# Connector.net
KiCad netlist of a schematic drawn in Altium Designer
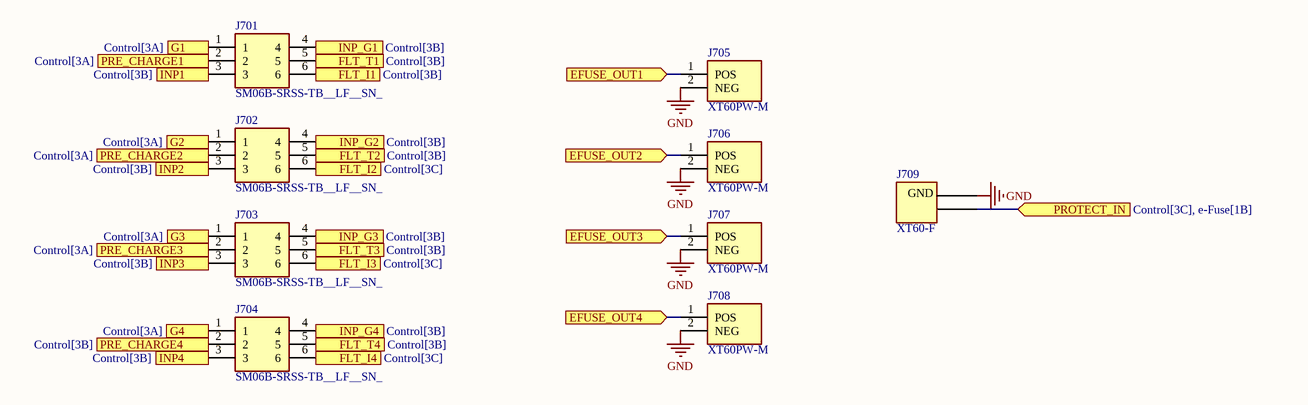
[diagram p0: Connector.SchDoc]

(export (version "E")
  (design (tool "Eeschema 10.0.6"))
  (components
    (comp (ref "J701")
      (value "SM06B-SRSS-TB__LF__SN_")
      (footprint "SamacSys:SM06B-SRSS-TB")
      (description "Connector")
      (fields (field (name "MANUFACTURER_PART_NUMBER") "SM06B-SRSS-TB (LF)(SN)"))
      (libsource (lib "*") (part "SM06B-SRSS-TB__LF__SN_"))
    )
    (comp (ref "J702")
      (value "SM06B-SRSS-TB__LF__SN_")
      (footprint "SamacSys:SM06B-SRSS-TB")
      (description "Connector")
      (fields (field (name "MANUFACTURER_PART_NUMBER") "SM06B-SRSS-TB (LF)(SN)"))
      (libsource (lib "*") (part "SM06B-SRSS-TB__LF__SN_"))
    )
    (comp (ref "J703")
      (value "SM06B-SRSS-TB__LF__SN_")
      (footprint "SamacSys:SM06B-SRSS-TB")
      (description "Connector")
      (fields (field (name "MANUFACTURER_PART_NUMBER") "SM06B-SRSS-TB (LF)(SN)"))
      (libsource (lib "*") (part "SM06B-SRSS-TB__LF__SN_"))
    )
    (comp (ref "J704")
      (value "SM06B-SRSS-TB__LF__SN_")
      (footprint "SamacSys:SM06B-SRSS-TB")
      (description "Connector")
      (fields (field (name "MANUFACTURER_PART_NUMBER") "SM06B-SRSS-TB (LF)(SN)"))
      (libsource (lib "*") (part "SM06B-SRSS-TB__LF__SN_"))
    )
    (comp (ref "J705")
      (value "XT60PW-M")
      (footprint "XT60PW-M")
      (description "Socket, DC supply, male, PIN: 2")
      (fields (field (name "MF") "AMASS") (field (name "SOURCE") "robit_connector.SchLib"))
      (libsource (lib "robit circuit") (part "XT60PW-M"))
    )
    (comp (ref "J706")
      (value "XT60PW-M")
      (footprint "XT60PW-M")
      (description "Socket, DC supply, male, PIN: 2")
      (fields (field (name "MF") "AMASS") (field (name "SOURCE") "robit_connector.SchLib"))
      (libsource (lib "robit circuit") (part "XT60PW-M"))
    )
    (comp (ref "J707")
      (value "XT60PW-M")
      (footprint "XT60PW-M")
      (description "Socket, DC supply, male, PIN: 2")
      (fields (field (name "MF") "AMASS") (field (name "SOURCE") "robit_connector.SchLib"))
      (libsource (lib "robit circuit") (part "XT60PW-M"))
    )
    (comp (ref "J708")
      (value "XT60PW-M")
      (footprint "XT60PW-M")
      (description "Socket, DC supply, male, PIN: 2")
      (fields (field (name "MF") "AMASS") (field (name "SOURCE") "robit_connector.SchLib"))
      (libsource (lib "robit circuit") (part "XT60PW-M"))
    )
    (comp (ref "J709")
      (value "XT60-F")
      (footprint "XT60_F")
      (description "XT60 connector")
      (libsource (lib "robit circuit") (part "XT60"))
    )
  )
  (nets
    (net (code "1") (name "/EFUSE_OUT1") (class "Default")
      (node (ref "J705") (pin "1") (pinfunction "POS_1") (pintype "passive"))
    )
    (net (code "2") (name "/EFUSE_OUT2") (class "Default")
      (node (ref "J706") (pin "1") (pinfunction "POS_1") (pintype "passive"))
    )
    (net (code "3") (name "/EFUSE_OUT3") (class "Default")
      (node (ref "J707") (pin "1") (pinfunction "POS_1") (pintype "passive"))
    )
    (net (code "4") (name "/EFUSE_OUT4") (class "Default")
      (node (ref "J708") (pin "1") (pinfunction "POS_1") (pintype "passive"))
    )
    (net (code "5") (name "/FLT_I1") (class "Default")
      (node (ref "J701") (pin "6") (pinfunction "6_6") (pintype "passive"))
    )
    (net (code "6") (name "/FLT_I2") (class "Default")
      (node (ref "J702") (pin "6") (pinfunction "6_6") (pintype "passive"))
    )
    (net (code "7") (name "/FLT_I3") (class "Default")
      (node (ref "J703") (pin "6") (pinfunction "6_6") (pintype "passive"))
    )
    (net (code "8") (name "/FLT_I4") (class "Default")
      (node (ref "J704") (pin "6") (pinfunction "6_6") (pintype "passive"))
    )
    (net (code "9") (name "/FLT_T1") (class "Default")
      (node (ref "J701") (pin "5") (pinfunction "5_5") (pintype "passive"))
    )
    (net (code "10") (name "/FLT_T2") (class "Default")
      (node (ref "J702") (pin "5") (pinfunction "5_5") (pintype "passive"))
    )
    (net (code "11") (name "/FLT_T3") (class "Default")
      (node (ref "J703") (pin "5") (pinfunction "5_5") (pintype "passive"))
    )
    (net (code "12") (name "/FLT_T4") (class "Default")
      (node (ref "J704") (pin "5") (pinfunction "5_5") (pintype "passive"))
    )
    (net (code "13") (name "/G1") (class "Default")
      (node (ref "J701") (pin "1") (pinfunction "1_1") (pintype "passive"))
    )
    (net (code "14") (name "/G2") (class "Default")
      (node (ref "J702") (pin "1") (pinfunction "1_1") (pintype "passive"))
    )
    (net (code "15") (name "/G3") (class "Default")
      (node (ref "J703") (pin "1") (pinfunction "1_1") (pintype "passive"))
    )
    (net (code "16") (name "/G4") (class "Default")
      (node (ref "J704") (pin "1") (pinfunction "1_1") (pintype "passive"))
    )
    (net (code "17") (name "/INP1") (class "Default")
      (node (ref "J701") (pin "3") (pinfunction "3_3") (pintype "passive"))
    )
    (net (code "18") (name "/INP2") (class "Default")
      (node (ref "J702") (pin "3") (pinfunction "3_3") (pintype "passive"))
    )
    (net (code "19") (name "/INP3") (class "Default")
      (node (ref "J703") (pin "3") (pinfunction "3_3") (pintype "passive"))
    )
    (net (code "20") (name "/INP4") (class "Default")
      (node (ref "J704") (pin "3") (pinfunction "3_3") (pintype "passive"))
    )
    (net (code "21") (name "/INP_G1") (class "Default")
      (node (ref "J701") (pin "4") (pinfunction "4_4") (pintype "passive"))
    )
    (net (code "22") (name "/INP_G2") (class "Default")
      (node (ref "J702") (pin "4") (pinfunction "4_4") (pintype "passive"))
    )
    (net (code "23") (name "/INP_G3") (class "Default")
      (node (ref "J703") (pin "4") (pinfunction "4_4") (pintype "passive"))
    )
    (net (code "24") (name "/INP_G4") (class "Default")
      (node (ref "J704") (pin "4") (pinfunction "4_4") (pintype "passive"))
    )
    (net (code "25") (name "/PRE_CHARGE1") (class "Default")
      (node (ref "J701") (pin "2") (pinfunction "2_2") (pintype "passive"))
    )
    (net (code "26") (name "/PRE_CHARGE2") (class "Default")
      (node (ref "J702") (pin "2") (pinfunction "2_2") (pintype "passive"))
    )
    (net (code "27") (name "/PRE_CHARGE3") (class "Default")
      (node (ref "J703") (pin "2") (pinfunction "2_2") (pintype "passive"))
    )
    (net (code "28") (name "/PRE_CHARGE4") (class "Default")
      (node (ref "J704") (pin "2") (pinfunction "2_2") (pintype "passive"))
    )
    (net (code "29") (name "/PROTECT_IN") (class "Default")
      (node (ref "J709") (pin "2") (pinfunction "2_2") (pintype "passive"))
    )
    (net (code "30") (name "GND") (class "Default")
      (node (ref "J705") (pin "2") (pinfunction "NEG_2") (pintype "passive"))
      (node (ref "J706") (pin "2") (pinfunction "NEG_2") (pintype "passive"))
      (node (ref "J707") (pin "2") (pinfunction "NEG_2") (pintype "passive"))
      (node (ref "J708") (pin "2") (pinfunction "NEG_2") (pintype "passive"))
      (node (ref "J709") (pin "1") (pinfunction "1_1") (pintype "passive"))
    )
  )
)
